# M901B.net
KiCad netlist of a schematic drawn in EAGLE
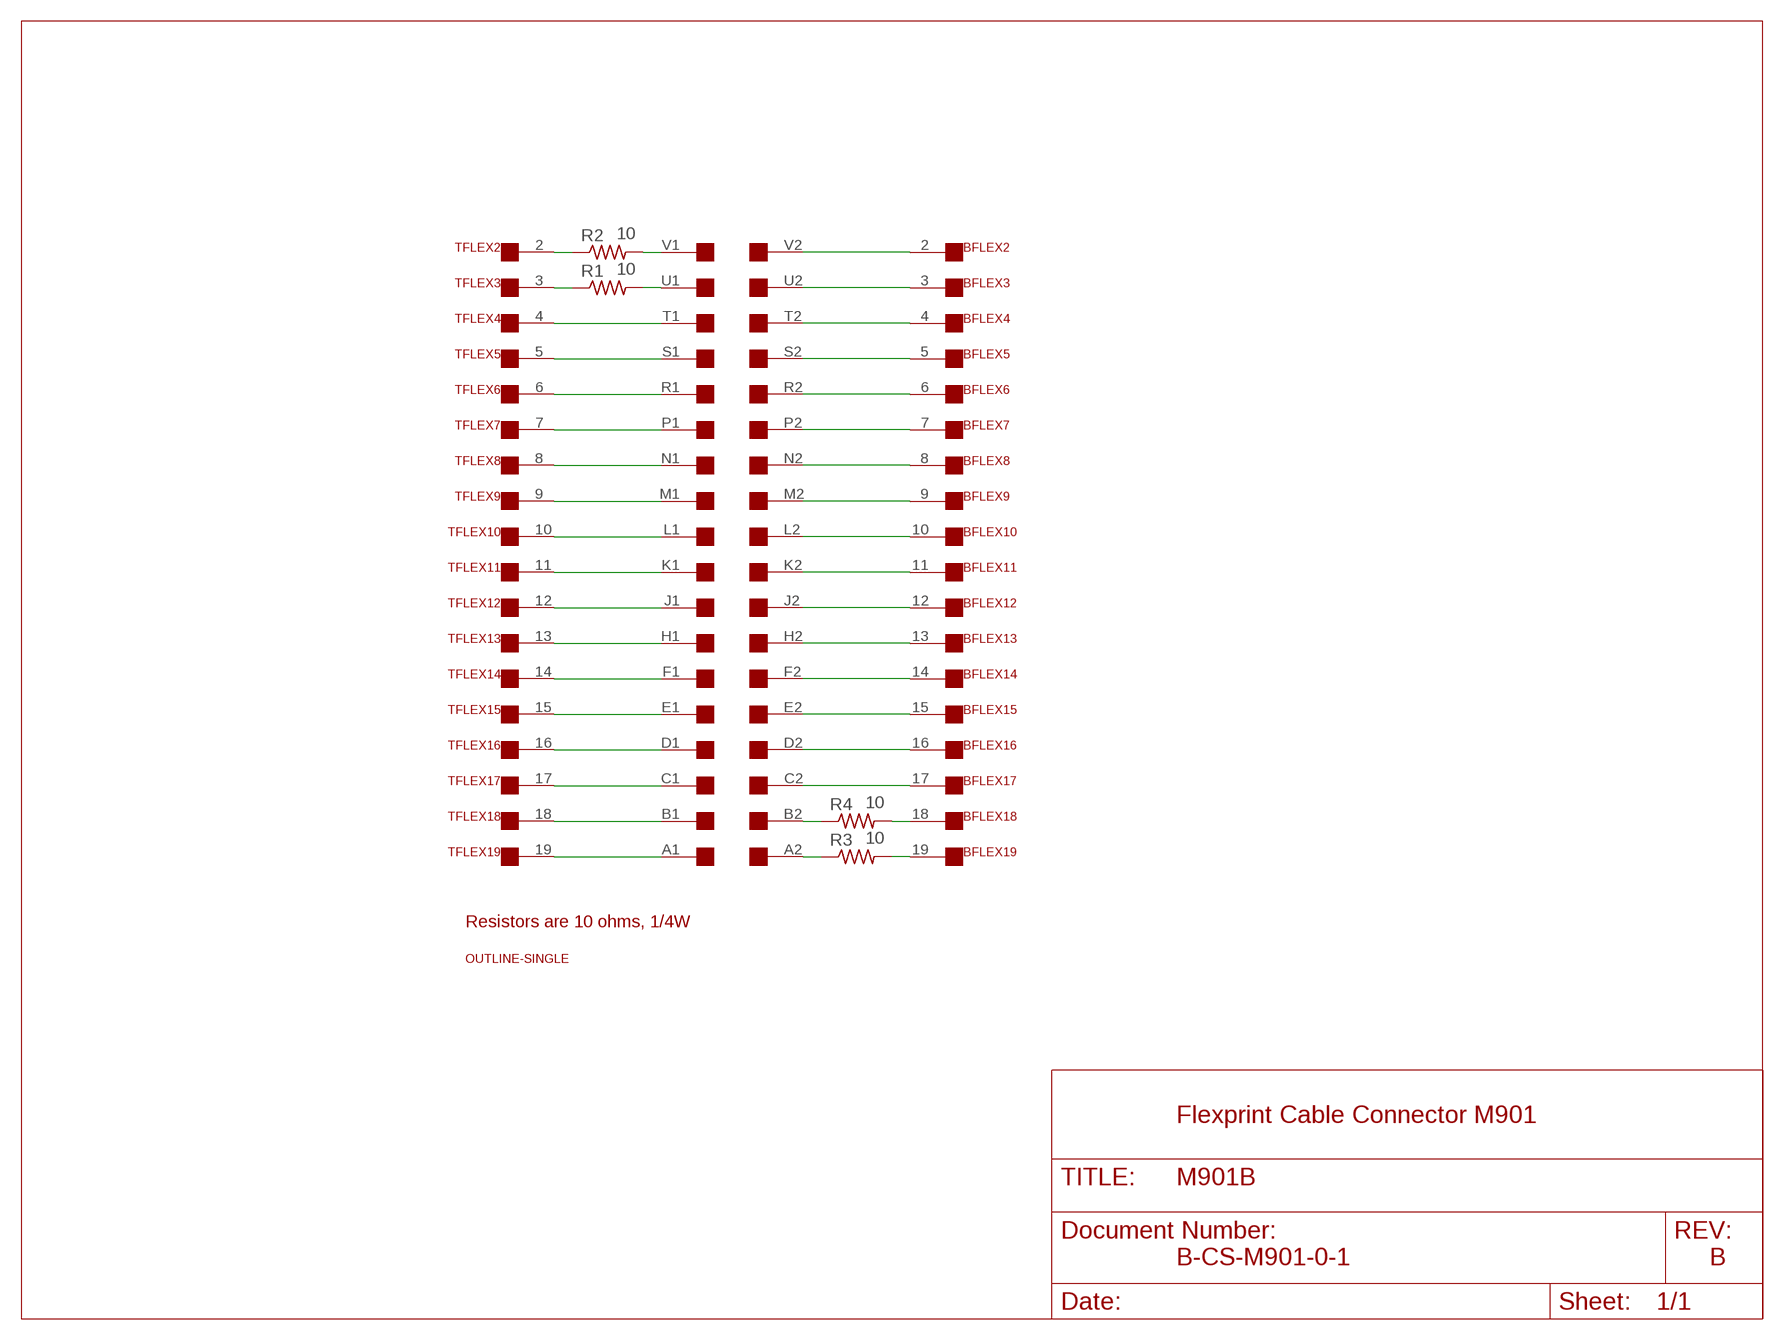
[diagram p0: schematic, sheet 1]

(export (version "E")
  (design (tool "Eeschema 10.0.6"))
  (components
    (comp (ref "BFLEX")
      (value "FLEX19")
      (footprint "eagle-import:FLEX19")
      (libsource (lib "eagle-import") (part "FLEX19"))
    )
    (comp (ref "R1")
      (value "10")
      (footprint "eagle-import:0207_10")
      (libsource (lib "eagle-import") (part "R-US_0207/10"))
    )
    (comp (ref "R2")
      (value "10")
      (footprint "eagle-import:0207_10")
      (libsource (lib "eagle-import") (part "R-US_0207/10"))
    )
    (comp (ref "R3")
      (value "10")
      (footprint "eagle-import:0207_10")
      (libsource (lib "eagle-import") (part "R-US_0207/10"))
    )
    (comp (ref "R4")
      (value "10")
      (footprint "eagle-import:0207_10")
      (libsource (lib "eagle-import") (part "R-US_0207/10"))
    )
    (comp (ref "TFLEX")
      (value "FLEX19")
      (footprint "eagle-import:FLEX19")
      (libsource (lib "eagle-import") (part "FLEX19"))
    )
    (comp (ref "U$1")
      (value "SINGLE")
      (footprint "eagle-import:EDGE-CON2")
      (libsource (lib "eagle-import") (part "SINGLE"))
    )
    (comp (ref "U$2")
      (value "OUTLINE-SINGLE")
      (footprint "eagle-import:SINGLE")
      (libsource (lib "eagle-import") (part "OUTLINE-SINGLE"))
    )
  )
  (nets
    (net (code "1") (name "Net-(BFLEXB-1)") (class "Default")
      (node (ref "BFLEX") (pin "10") (pinfunction "1_10") (pintype "passive"))
      (node (ref "U$1") (pin "L2") (pinfunction "1_L2") (pintype "bidirectional"))
    )
    (net (code "2") (name "Net-(BFLEXC-1)") (class "Default")
      (node (ref "BFLEX") (pin "11") (pinfunction "1_11") (pintype "passive"))
      (node (ref "U$1") (pin "K2") (pinfunction "1_K2") (pintype "bidirectional"))
    )
    (net (code "3") (name "Net-(BFLEXD-1)") (class "Default")
      (node (ref "BFLEX") (pin "12") (pinfunction "1_12") (pintype "passive"))
      (node (ref "U$1") (pin "J2") (pinfunction "1_J2") (pintype "bidirectional"))
    )
    (net (code "4") (name "Net-(BFLEXE-1)") (class "Default")
      (node (ref "BFLEX") (pin "13") (pinfunction "1_13") (pintype "passive"))
      (node (ref "U$1") (pin "H2") (pinfunction "1_H2") (pintype "bidirectional"))
    )
    (net (code "5") (name "Net-(BFLEXF-1)") (class "Default")
      (node (ref "BFLEX") (pin "14") (pinfunction "1_14") (pintype "passive"))
      (node (ref "U$1") (pin "F2") (pinfunction "1_F2") (pintype "bidirectional"))
    )
    (net (code "6") (name "Net-(BFLEXG-1)") (class "Default")
      (node (ref "BFLEX") (pin "15") (pinfunction "1_15") (pintype "passive"))
      (node (ref "U$1") (pin "E2") (pinfunction "1_E2") (pintype "bidirectional"))
    )
    (net (code "7") (name "Net-(BFLEXH-1)") (class "Default")
      (node (ref "BFLEX") (pin "16") (pinfunction "1_16") (pintype "passive"))
      (node (ref "U$1") (pin "D2") (pinfunction "1_D2") (pintype "bidirectional"))
    )
    (net (code "8") (name "Net-(BFLEXI-1)") (class "Default")
      (node (ref "BFLEX") (pin "17") (pinfunction "1_17") (pintype "passive"))
      (node (ref "U$1") (pin "C2") (pinfunction "1_C2") (pintype "bidirectional"))
    )
    (net (code "9") (name "Net-(BFLEXJ-1)") (class "Default")
      (node (ref "BFLEX") (pin "18") (pinfunction "1_18") (pintype "passive"))
      (node (ref "R4") (pin "2") (pinfunction "2_2") (pintype "passive"))
    )
    (net (code "10") (name "Net-(BFLEXK-1)") (class "Default")
      (node (ref "BFLEX") (pin "19") (pinfunction "1_19") (pintype "passive"))
      (node (ref "R3") (pin "2") (pinfunction "2_2") (pintype "passive"))
    )
    (net (code "11") (name "Net-(BFLEXL-1)") (class "Default")
      (node (ref "BFLEX") (pin "2") (pinfunction "1_2") (pintype "passive"))
      (node (ref "U$1") (pin "V2") (pinfunction "1_V2") (pintype "bidirectional"))
    )
    (net (code "12") (name "Net-(BFLEXM-1)") (class "Default")
      (node (ref "BFLEX") (pin "3") (pinfunction "1_3") (pintype "passive"))
      (node (ref "U$1") (pin "U2") (pinfunction "1_U2") (pintype "bidirectional"))
    )
    (net (code "13") (name "Net-(BFLEXN-1)") (class "Default")
      (node (ref "BFLEX") (pin "4") (pinfunction "1_4") (pintype "passive"))
      (node (ref "U$1") (pin "T2") (pinfunction "1_T2") (pintype "bidirectional"))
    )
    (net (code "14") (name "Net-(BFLEXO-1)") (class "Default")
      (node (ref "BFLEX") (pin "5") (pinfunction "1_5") (pintype "passive"))
      (node (ref "U$1") (pin "S2") (pinfunction "1_S2") (pintype "bidirectional"))
    )
    (net (code "15") (name "Net-(BFLEXP-1)") (class "Default")
      (node (ref "BFLEX") (pin "6") (pinfunction "1_6") (pintype "passive"))
      (node (ref "U$1") (pin "R2") (pinfunction "1_R2") (pintype "bidirectional"))
    )
    (net (code "16") (name "Net-(BFLEXQ-1)") (class "Default")
      (node (ref "BFLEX") (pin "7") (pinfunction "1_7") (pintype "passive"))
      (node (ref "U$1") (pin "P2") (pinfunction "1_P2") (pintype "bidirectional"))
    )
    (net (code "17") (name "Net-(BFLEXR-1)") (class "Default")
      (node (ref "BFLEX") (pin "8") (pinfunction "1_8") (pintype "passive"))
      (node (ref "U$1") (pin "N2") (pinfunction "1_N2") (pintype "bidirectional"))
    )
    (net (code "18") (name "Net-(BFLEXS-1)") (class "Default")
      (node (ref "BFLEX") (pin "9") (pinfunction "1_9") (pintype "passive"))
      (node (ref "U$1") (pin "M2") (pinfunction "1_M2") (pintype "bidirectional"))
    )
    (net (code "19") (name "Net-(TFLEXB-1)") (class "Default")
      (node (ref "TFLEX") (pin "10") (pinfunction "1_10") (pintype "passive"))
      (node (ref "U$1") (pin "L1") (pinfunction "1_L1") (pintype "bidirectional"))
    )
    (net (code "20") (name "Net-(TFLEXC-1)") (class "Default")
      (node (ref "TFLEX") (pin "11") (pinfunction "1_11") (pintype "passive"))
      (node (ref "U$1") (pin "K1") (pinfunction "1_K1") (pintype "bidirectional"))
    )
    (net (code "21") (name "Net-(TFLEXD-1)") (class "Default")
      (node (ref "TFLEX") (pin "12") (pinfunction "1_12") (pintype "passive"))
      (node (ref "U$1") (pin "J1") (pinfunction "1_J1") (pintype "bidirectional"))
    )
    (net (code "22") (name "Net-(TFLEXE-1)") (class "Default")
      (node (ref "TFLEX") (pin "13") (pinfunction "1_13") (pintype "passive"))
      (node (ref "U$1") (pin "H1") (pinfunction "1_H1") (pintype "bidirectional"))
    )
    (net (code "23") (name "Net-(TFLEXF-1)") (class "Default")
      (node (ref "TFLEX") (pin "14") (pinfunction "1_14") (pintype "passive"))
      (node (ref "U$1") (pin "F1") (pinfunction "1_F1") (pintype "bidirectional"))
    )
    (net (code "24") (name "Net-(TFLEXG-1)") (class "Default")
      (node (ref "TFLEX") (pin "15") (pinfunction "1_15") (pintype "passive"))
      (node (ref "U$1") (pin "E1") (pinfunction "1_E1") (pintype "bidirectional"))
    )
    (net (code "25") (name "Net-(TFLEXH-1)") (class "Default")
      (node (ref "TFLEX") (pin "16") (pinfunction "1_16") (pintype "passive"))
      (node (ref "U$1") (pin "D1") (pinfunction "1_D1") (pintype "bidirectional"))
    )
    (net (code "26") (name "Net-(TFLEXI-1)") (class "Default")
      (node (ref "TFLEX") (pin "17") (pinfunction "1_17") (pintype "passive"))
      (node (ref "U$1") (pin "C1") (pinfunction "1_C1") (pintype "bidirectional"))
    )
    (net (code "27") (name "Net-(TFLEXJ-1)") (class "Default")
      (node (ref "TFLEX") (pin "18") (pinfunction "1_18") (pintype "passive"))
      (node (ref "U$1") (pin "B1") (pinfunction "1_B1") (pintype "bidirectional"))
    )
    (net (code "28") (name "Net-(TFLEXK-1)") (class "Default")
      (node (ref "TFLEX") (pin "19") (pinfunction "1_19") (pintype "passive"))
      (node (ref "U$1") (pin "A1") (pinfunction "1_A1") (pintype "bidirectional"))
    )
    (net (code "29") (name "Net-(TFLEXL-1)") (class "Default")
      (node (ref "R2") (pin "1") (pinfunction "1_1") (pintype "passive"))
      (node (ref "TFLEX") (pin "2") (pinfunction "1_2") (pintype "passive"))
    )
    (net (code "30") (name "Net-(TFLEXM-1)") (class "Default")
      (node (ref "R1") (pin "1") (pinfunction "1_1") (pintype "passive"))
      (node (ref "TFLEX") (pin "3") (pinfunction "1_3") (pintype "passive"))
    )
    (net (code "31") (name "Net-(TFLEXN-1)") (class "Default")
      (node (ref "TFLEX") (pin "4") (pinfunction "1_4") (pintype "passive"))
      (node (ref "U$1") (pin "T1") (pinfunction "1_T1") (pintype "bidirectional"))
    )
    (net (code "32") (name "Net-(TFLEXO-1)") (class "Default")
      (node (ref "TFLEX") (pin "5") (pinfunction "1_5") (pintype "passive"))
      (node (ref "U$1") (pin "S1") (pinfunction "1_S1") (pintype "bidirectional"))
    )
    (net (code "33") (name "Net-(TFLEXP-1)") (class "Default")
      (node (ref "TFLEX") (pin "6") (pinfunction "1_6") (pintype "passive"))
      (node (ref "U$1") (pin "R1") (pinfunction "1_R1") (pintype "bidirectional"))
    )
    (net (code "34") (name "Net-(TFLEXQ-1)") (class "Default")
      (node (ref "TFLEX") (pin "7") (pinfunction "1_7") (pintype "passive"))
      (node (ref "U$1") (pin "P1") (pinfunction "1_P1") (pintype "bidirectional"))
    )
    (net (code "35") (name "Net-(TFLEXR-1)") (class "Default")
      (node (ref "TFLEX") (pin "8") (pinfunction "1_8") (pintype "passive"))
      (node (ref "U$1") (pin "N1") (pinfunction "1_N1") (pintype "bidirectional"))
    )
    (net (code "36") (name "Net-(TFLEXS-1)") (class "Default")
      (node (ref "TFLEX") (pin "9") (pinfunction "1_9") (pintype "passive"))
      (node (ref "U$1") (pin "M1") (pinfunction "1_M1") (pintype "bidirectional"))
    )
    (net (code "37") (name "Net-(U$1AG-1)") (class "Default")
      (node (ref "R1") (pin "2") (pinfunction "2_2") (pintype "passive"))
      (node (ref "U$1") (pin "U1") (pinfunction "1_U1") (pintype "bidirectional"))
    )
    (net (code "38") (name "Net-(U$1AI-1)") (class "Default")
      (node (ref "R2") (pin "2") (pinfunction "2_2") (pintype "passive"))
      (node (ref "U$1") (pin "V1") (pinfunction "1_V1") (pintype "bidirectional"))
    )
    (net (code "39") (name "Net-(U$1B-1)") (class "Default")
      (node (ref "R3") (pin "1") (pinfunction "1_1") (pintype "passive"))
      (node (ref "U$1") (pin "A2") (pinfunction "1_A2") (pintype "bidirectional"))
    )
    (net (code "40") (name "Net-(U$1D-1)") (class "Default")
      (node (ref "R4") (pin "1") (pinfunction "1_1") (pintype "passive"))
      (node (ref "U$1") (pin "B2") (pinfunction "1_B2") (pintype "bidirectional"))
    )
  )
)
